# Level_Shifter.net
KiCad netlist of a schematic drawn in Altium Designer
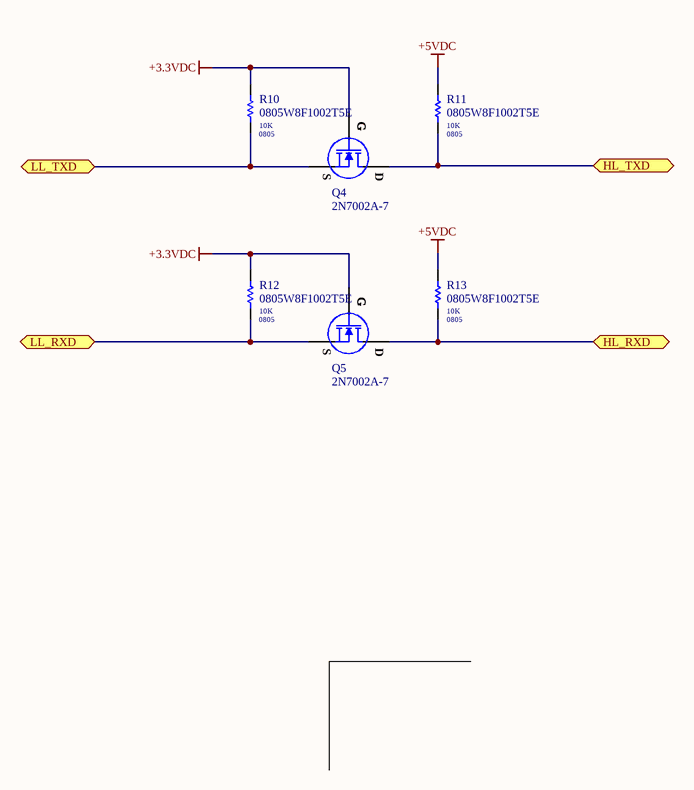
[diagram p0: Level_Shifter.SchDoc]

(export (version "E")
  (design (tool "Eeschema 10.0.6"))
  (components
    (comp (ref "Q4")
      (value "2N7002A-7")
      (footprint "SuperSOT-3")
      (description "N-Channel MOSFET")
      (fields (field (name "LCSC PART") "C139446") (field (name "PUBLISHER") "Altium Limited"))
      (libsource (lib "") (part "MOSFET N channel_1"))
    )
    (comp (ref "Q5")
      (value "2N7002A-7")
      (footprint "SuperSOT-3")
      (description "N-Channel MOSFET")
      (fields (field (name "LCSC PART") "C139446") (field (name "PUBLISHER") "Altium Limited"))
      (libsource (lib "IDETEC LIB") (part "MOSFET N channel"))
    )
    (comp (ref "R10")
      (value "0805W8F1002T5E")
      (footprint "RES-0805")
      (description "Resistor")
      (fields
        (field (name "ALTIUM_VALUE") "10K")
        (field (name "PACKAGE") "0805")
        (field (name "LCSC PART") "C17414")
        (field (name "PUBLISHER") "Altium Limited")
      )
      (libsource (lib "IDETEC LIB") (part "Resistor"))
    )
    (comp (ref "R11")
      (value "0805W8F1002T5E")
      (footprint "RES-0805")
      (description "Resistor")
      (fields
        (field (name "ALTIUM_VALUE") "10K")
        (field (name "PACKAGE") "0805")
        (field (name "LCSC PART") "C17414")
        (field (name "PUBLISHER") "Altium Limited")
      )
      (libsource (lib "IDETEC LIB") (part "Resistor"))
    )
    (comp (ref "R12")
      (value "0805W8F1002T5E")
      (footprint "RES-0805")
      (description "Resistor")
      (fields
        (field (name "ALTIUM_VALUE") "10K")
        (field (name "PACKAGE") "0805")
        (field (name "LCSC PART") "C17414")
        (field (name "PUBLISHER") "Altium Limited")
      )
      (libsource (lib "IDETEC LIB") (part "Resistor"))
    )
    (comp (ref "R13")
      (value "0805W8F1002T5E")
      (footprint "RES-0805")
      (description "Resistor")
      (fields
        (field (name "ALTIUM_VALUE") "10K")
        (field (name "PACKAGE") "0805")
        (field (name "LCSC PART") "C17414")
        (field (name "PUBLISHER") "Altium Limited")
      )
      (libsource (lib "IDETEC LIB") (part "Resistor"))
    )
  )
  (nets
    (net (code "1") (name "+3.3VDC") (class "Default")
      (node (ref "Q4") (pin "2") (pinfunction "G_2") (pintype "passive"))
      (node (ref "Q5") (pin "2") (pinfunction "G_2") (pintype "passive"))
      (node (ref "R10") (pin "2") (pinfunction "2_2") (pintype "passive"))
      (node (ref "R12") (pin "2") (pinfunction "2_2") (pintype "passive"))
    )
    (net (code "2") (name "+5VDC") (class "Default")
      (node (ref "R11") (pin "2") (pinfunction "2_2") (pintype "passive"))
      (node (ref "R13") (pin "2") (pinfunction "2_2") (pintype "passive"))
    )
    (net (code "3") (name "/HL_RXD") (class "Default")
      (node (ref "Q5") (pin "3") (pinfunction "D_3") (pintype "passive"))
      (node (ref "R13") (pin "1") (pinfunction "1_1") (pintype "passive"))
    )
    (net (code "4") (name "/HL_TXD") (class "Default")
      (node (ref "Q4") (pin "3") (pinfunction "D_3") (pintype "passive"))
      (node (ref "R11") (pin "1") (pinfunction "1_1") (pintype "passive"))
    )
    (net (code "5") (name "/LL_RXD") (class "Default")
      (node (ref "Q5") (pin "1") (pinfunction "S_1") (pintype "passive"))
      (node (ref "R12") (pin "1") (pinfunction "1_1") (pintype "passive"))
    )
    (net (code "7") (name "/LL_TXD") (class "Default")
      (node (ref "Q4") (pin "1") (pinfunction "S_1") (pintype "passive"))
      (node (ref "R10") (pin "1") (pinfunction "1_1") (pintype "passive"))
    )
  )
)
